# Gleichrichter.net
KiCad netlist of a schematic drawn in EAGLE
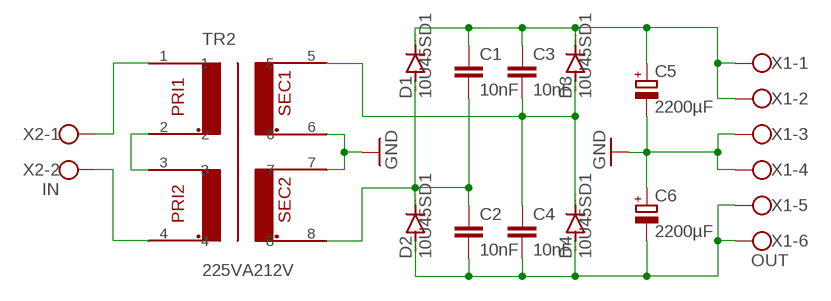
[diagram p0: schematic, sheet 1]

(export (version "E")
  (design (tool "Eeschema 10.0.6"))
  (components
    (comp (ref "C1")
      (value "10nF")
      (footprint "eagle-import:C050-024X044")
      (libsource (lib "eagle-import") (part "C-EU050-024X044"))
    )
    (comp (ref "C2")
      (value "10nF")
      (footprint "eagle-import:C050-024X044")
      (libsource (lib "eagle-import") (part "C-EU050-024X044"))
    )
    (comp (ref "C3")
      (value "10nF")
      (footprint "eagle-import:C050-024X044")
      (libsource (lib "eagle-import") (part "C-EU050-024X044"))
    )
    (comp (ref "C4")
      (value "10nF")
      (footprint "eagle-import:C050-024X044")
      (libsource (lib "eagle-import") (part "C-EU050-024X044"))
    )
    (comp (ref "C5")
      (value "2200µF")
      (footprint "eagle-import:E5-13")
      (libsource (lib "eagle-import") (part "CPOL-EUE5-13"))
    )
    (comp (ref "C6")
      (value "2200µF")
      (footprint "eagle-import:E5-13")
      (libsource (lib "eagle-import") (part "CPOL-EUE5-13"))
    )
    (comp (ref "D1")
      (value "10U45SD1")
      (footprint "eagle-import:DO201-15")
      (libsource (lib "eagle-import") (part "1N5400"))
    )
    (comp (ref "D2")
      (value "10U45SD1")
      (footprint "eagle-import:DO201-15")
      (libsource (lib "eagle-import") (part "1N5400"))
    )
    (comp (ref "D3")
      (value "10U45SD1")
      (footprint "eagle-import:DO201-15")
      (libsource (lib "eagle-import") (part "1N5400"))
    )
    (comp (ref "D4")
      (value "10U45SD1")
      (footprint "eagle-import:DO201-15")
      (libsource (lib "eagle-import") (part "1N5400"))
    )
    (comp (ref "TR2")
      (value "225VA212V")
      (footprint "eagle-import:RKD225-2X12")
      (libsource (lib "eagle-import") (part "225VA212V"))
    )
    (comp (ref "X1")
      (value "OUT")
      (footprint "eagle-import:W237-6")
      (libsource (lib "eagle-import") (part "W237-6"))
    )
    (comp (ref "X2")
      (value "IN")
      (footprint "eagle-import:W237-102")
      (fields (field (name "MPN") "237-102"))
      (libsource (lib "eagle-import") (part "W237-102"))
    )
  )
  (nets
    (net (code "1") (name "GND") (class "Default")
      (node (ref "C5") (pin "-") (pinfunction "-_-") (pintype "passive"))
      (node (ref "C6") (pin "+") (pinfunction "+_+") (pintype "passive"))
      (node (ref "TR2") (pin "6") (pinfunction "6_6") (pintype "bidirectional"))
      (node (ref "TR2") (pin "7") (pinfunction "7_7") (pintype "bidirectional"))
      (node (ref "X1") (pin "3") (pinfunction "KL_3") (pintype "passive"))
      (node (ref "X1") (pin "4") (pinfunction "KL_4") (pintype "passive"))
    )
    (net (code "2") (name "Net-(C1-Pad2)") (class "Default")
      (node (ref "C1") (pin "2") (pinfunction "2_2") (pintype "passive"))
      (node (ref "C2") (pin "1") (pinfunction "1_1") (pintype "passive"))
      (node (ref "D1") (pin "A") (pinfunction "A_A") (pintype "passive"))
      (node (ref "D2") (pin "C") (pinfunction "C_C") (pintype "passive"))
      (node (ref "TR2") (pin "8") (pinfunction "8_8") (pintype "bidirectional"))
    )
    (net (code "3") (name "Net-(C3-Pad2)") (class "Default")
      (node (ref "C3") (pin "2") (pinfunction "2_2") (pintype "passive"))
      (node (ref "C4") (pin "1") (pinfunction "1_1") (pintype "passive"))
      (node (ref "D3") (pin "A") (pinfunction "A_A") (pintype "passive"))
      (node (ref "D4") (pin "C") (pinfunction "C_C") (pintype "passive"))
      (node (ref "TR2") (pin "5") (pinfunction "5_5") (pintype "bidirectional"))
    )
    (net (code "4") (name "Net-(TR2-Pad2)") (class "Default")
      (node (ref "TR2") (pin "2") (pinfunction "2_2") (pintype "bidirectional"))
      (node (ref "TR2") (pin "3") (pinfunction "3_3") (pintype "bidirectional"))
    )
    (net (code "5") (name "Net-(X1A-KL)") (class "Default")
      (node (ref "C1") (pin "1") (pinfunction "1_1") (pintype "passive"))
      (node (ref "C3") (pin "1") (pinfunction "1_1") (pintype "passive"))
      (node (ref "C5") (pin "+") (pinfunction "+_+") (pintype "passive"))
      (node (ref "D1") (pin "C") (pinfunction "C_C") (pintype "passive"))
      (node (ref "D3") (pin "C") (pinfunction "C_C") (pintype "passive"))
      (node (ref "X1") (pin "1") (pinfunction "KL_1") (pintype "passive"))
      (node (ref "X1") (pin "2") (pinfunction "KL_2") (pintype "passive"))
    )
    (net (code "6") (name "Net-(X1E-KL)") (class "Default")
      (node (ref "C2") (pin "2") (pinfunction "2_2") (pintype "passive"))
      (node (ref "C4") (pin "2") (pinfunction "2_2") (pintype "passive"))
      (node (ref "C6") (pin "-") (pinfunction "-_-") (pintype "passive"))
      (node (ref "D2") (pin "A") (pinfunction "A_A") (pintype "passive"))
      (node (ref "D4") (pin "A") (pinfunction "A_A") (pintype "passive"))
      (node (ref "X1") (pin "5") (pinfunction "KL_5") (pintype "passive"))
      (node (ref "X1") (pin "6") (pinfunction "KL_6") (pintype "passive"))
    )
    (net (code "7") (name "Net-(X2A-KL)") (class "Default")
      (node (ref "TR2") (pin "1") (pinfunction "1_1") (pintype "bidirectional"))
      (node (ref "X2") (pin "1") (pinfunction "KL_1") (pintype "passive"))
    )
    (net (code "8") (name "Net-(X2B-KL)") (class "Default")
      (node (ref "TR2") (pin "4") (pinfunction "4_4") (pintype "bidirectional"))
      (node (ref "X2") (pin "2") (pinfunction "KL_2") (pintype "passive"))
    )
  )
)
